# Arduino_RGB_lamp_beads.net
KiCad netlist of a schematic drawn in Altium Designer
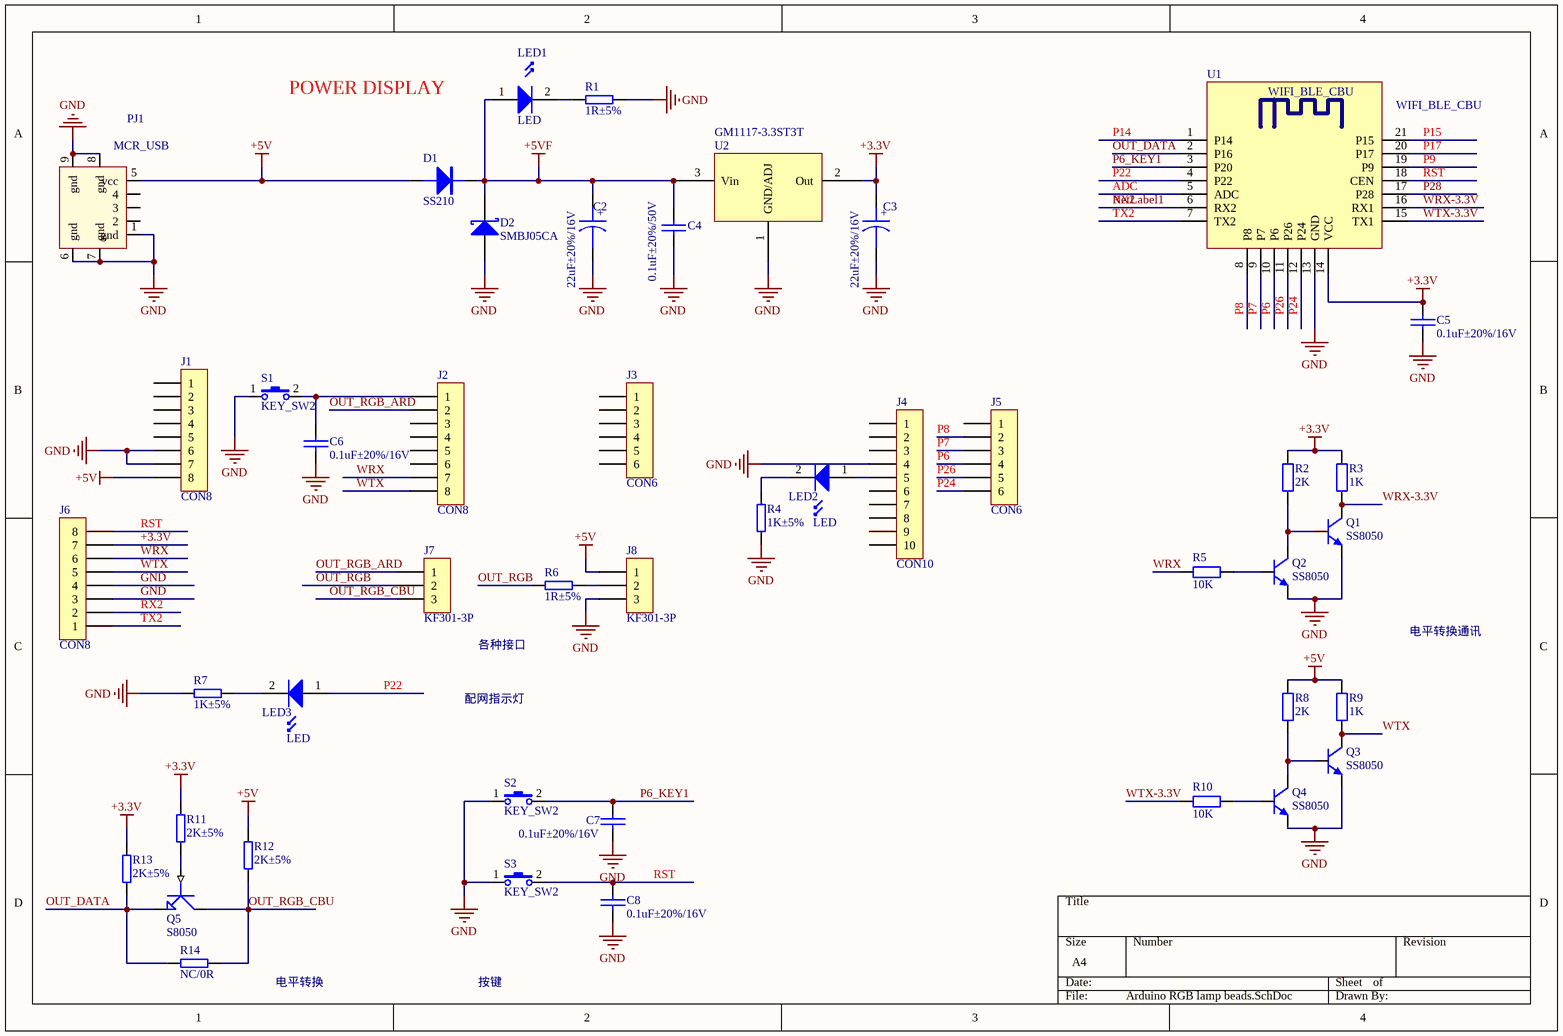
[diagram p0: Arduino RGB lamp beads.SchDoc]

(export (version "E")
  (design (tool "Eeschema 10.0.6"))
  (components
    (comp (ref "C2")
      (value "22uF±20%/16V")
      (footprint "CD B(3528)")
      (description "Capacitor")
      (libsource (lib "*") (part "CAPACITOR POL"))
    )
    (comp (ref "C3")
      (value "22uF±20%/16V")
      (footprint "CD B(3528)")
      (description "Capacitor")
      (libsource (lib "*") (part "CAPACITOR POL"))
    )
    (comp (ref "C4")
      (value "0.1uF±20%/50V")
      (footprint "C 0603_M")
      (description "Capacitor")
      (libsource (lib "昊华元件库sch") (part "CAP"))
    )
    (comp (ref "C5")
      (value "0.1uF±20%/16V")
      (footprint "C 0603_M")
      (description "Capacitor")
      (libsource (lib "昊华元件库sch") (part "CAP"))
    )
    (comp (ref "C6")
      (value "0.1uF±20%/16V")
      (footprint "C 0603_M")
      (description "Capacitor")
      (libsource (lib "昊华元件库sch") (part "CAP"))
    )
    (comp (ref "C7")
      (value "0.1uF±20%/16V")
      (footprint "C 0603_M")
      (description "Capacitor")
      (libsource (lib "昊华元件库sch") (part "CAP"))
    )
    (comp (ref "C8")
      (value "0.1uF±20%/16V")
      (footprint "C 0603_M")
      (description "Capacitor")
      (libsource (lib "昊华元件库sch") (part "CAP"))
    )
    (comp (ref "D1")
      (value "SS210")
      (footprint "SMB")
      (description "Diode")
      (libsource (lib "小马元件库sch") (part "Diode1"))
    )
    (comp (ref "D2")
      (value "SMBJ05CA")
      (footprint "SMB")
      (description "Schottky Diode")
      (fields (field (name "MFR") "Toshiba"))
      (libsource (lib "Miscellaneous Devices") (part "D Schottky"))
    )
    (comp (ref "J1")
      (value "CON8")
      (footprint "HDR2.54-LI-8P")
      (description "Connector")
      (libsource (lib "小马元件库sch") (part "CON8"))
    )
    (comp (ref "J2")
      (value "CON8")
      (footprint "HDR2.54-LI-8P")
      (description "Connector")
      (libsource (lib "小马元件库sch") (part "CON8"))
    )
    (comp (ref "J3")
      (value "CON6")
      (footprint "HDR2.54-LI-6P")
      (description "Connector")
      (libsource (lib "小马元件库sch") (part "CON6"))
    )
    (comp (ref "J4")
      (value "CON10")
      (footprint "HDR2.54-LI-10P")
      (description "Connector")
      (libsource (lib "小马元件库sch") (part "CON10"))
    )
    (comp (ref "J5")
      (value "CON6")
      (footprint "HDR2.54-LI-6P")
      (description "Connector")
      (libsource (lib "小马元件库sch") (part "CON6"))
    )
    (comp (ref "J6")
      (value "CON8")
      (footprint "HDR2.54-LI-8P")
      (description "Connector")
      (libsource (lib "") (part "CON8_1"))
    )
    (comp (ref "J7")
      (value "KF301-3P")
      (footprint "XH2.54-LI-3P")
      (description "Connector")
      (libsource (lib "小马元件库sch") (part "CON3"))
    )
    (comp (ref "J8")
      (value "KF301-3P")
      (footprint "XH2.54-LI-3P")
      (description "Connector")
      (libsource (lib "小马元件库sch") (part "CON3"))
    )
    (comp (ref "LED1")
      (value "LED")
      (footprint "LED 0603G")
      (fields (field (name "PUBLISHER") "*"))
      (libsource (lib "小马元件库sch") (part "LED"))
    )
    (comp (ref "LED2")
      (value "LED")
      (footprint "LED 0603G")
      (fields (field (name "PUBLISHER") "*"))
      (libsource (lib "小马元件库sch") (part "LED"))
    )
    (comp (ref "LED3")
      (value "LED")
      (footprint "LED 0603G")
      (fields (field (name "PUBLISHER") "*"))
      (libsource (lib "小马元件库sch") (part "LED"))
    )
    (comp (ref "PJ1")
      (value "MCR_USB")
      (footprint "USB-MICRO_E")
      (fields (field (name "PUBLISHER") "*"))
      (libsource (lib "昊华元件库sch") (part "MCR_USB"))
    )
    (comp (ref "Q1")
      (value "SS8050")
      (footprint "SOT23-3M")
      (description "高频放大-NPN型")
      (fields (field (name "版权归属") "源创客"))
      (libsource (lib "6.2   - 三极管") (part "8050-SMD"))
    )
    (comp (ref "Q2")
      (value "SS8050")
      (footprint "SOT23-3M")
      (description "高频放大-NPN型")
      (fields (field (name "版权归属") "源创客"))
      (libsource (lib "6.2   - 三极管") (part "8050-SMD"))
    )
    (comp (ref "Q3")
      (value "SS8050")
      (footprint "SOT23-3M")
      (description "高频放大-NPN型")
      (fields (field (name "版权归属") "源创客"))
      (libsource (lib "6.2   - 三极管") (part "8050-SMD"))
    )
    (comp (ref "Q4")
      (value "SS8050")
      (footprint "SOT23-3M")
      (description "高频放大-NPN型")
      (fields (field (name "版权归属") "源创客"))
      (libsource (lib "6.2   - 三极管") (part "8050-SMD"))
    )
    (comp (ref "Q5")
      (value "S8050")
      (footprint "SOT-23-NPN")
      (description "NPN Transistor")
      (libsource (lib "小马元件库sch") (part "NPN"))
    )
    (comp (ref "R1") (value "1R±5%") (footprint "R 0603_M") (libsource (lib "昊华元件库sch") (part "RES5")))
    (comp (ref "R2")
      (value "2K")
      (footprint "R 0603_M")
      (description "贴片电阻")
      (fields (field (name "版权归属") "源创客"))
      (libsource (lib "3.1   - 电阻-电容-电感") (part "R"))
    )
    (comp (ref "R3")
      (value "1K")
      (footprint "R 0603_M")
      (description "贴片电阻")
      (fields (field (name "版权归属") "源创客"))
      (libsource (lib "3.1   - 电阻-电容-电感") (part "R"))
    )
    (comp (ref "R4") (value "1K±5%") (footprint "R 0603_M") (libsource (lib "昊华元件库sch") (part "RES5")))
    (comp (ref "R5")
      (value "10K")
      (footprint "R 0603_M")
      (description "贴片电阻")
      (fields (field (name "版权归属") "源创客"))
      (libsource (lib "3.1   - 电阻-电容-电感") (part "R"))
    )
    (comp (ref "R6") (value "1R±5%") (footprint "R 0603_M") (libsource (lib "昊华元件库sch") (part "RES5")))
    (comp (ref "R7") (value "1K±5%") (footprint "R 0603_M") (libsource (lib "昊华元件库sch") (part "RES5")))
    (comp (ref "R8")
      (value "2K")
      (footprint "R 0603_M")
      (description "贴片电阻")
      (fields (field (name "版权归属") "源创客"))
      (libsource (lib "3.1   - 电阻-电容-电感") (part "R"))
    )
    (comp (ref "R9")
      (value "1K")
      (footprint "R 0603_M")
      (description "贴片电阻")
      (fields (field (name "版权归属") "源创客"))
      (libsource (lib "3.1   - 电阻-电容-电感") (part "R"))
    )
    (comp (ref "R10")
      (value "10K")
      (footprint "R 0603_M")
      (description "贴片电阻")
      (fields (field (name "版权归属") "源创客"))
      (libsource (lib "3.1   - 电阻-电容-电感") (part "R"))
    )
    (comp (ref "R11") (value "2K±5%") (footprint "R 0603_M") (libsource (lib "昊华元件库sch") (part "RES5")))
    (comp (ref "R12") (value "2K±5%") (footprint "R 0603_M") (libsource (lib "昊华元件库sch") (part "RES5")))
    (comp (ref "R13") (value "2K±5%") (footprint "R 0603_M") (libsource (lib "昊华元件库sch") (part "RES5")))
    (comp (ref "R14") (value "NC/0R") (footprint "R 0603_M") (libsource (lib "昊华元件库sch") (part "RES5")))
    (comp (ref "S1")
      (value "KEY_SW2")
      (footprint "TSW SMD-4*4*1.5")
      (libsource (lib "小马元件库sch") (part "KEY_SW2"))
    )
    (comp (ref "S2") (value "KEY_SW2") (footprint "KEY4-SMD") (libsource (lib "小马元件库sch") (part "KEY_SW2")))
    (comp (ref "S3") (value "KEY_SW2") (footprint "KEY4-SMD") (libsource (lib "小马元件库sch") (part "KEY_SW2")))
    (comp (ref "U1")
      (value "WIFI_BLE_CBU")
      (footprint "WIFI_BLE_CBU")
      (description "Module")
      (libsource (lib "TYModeSchlib V03") (part "WIFI_BLE_CBU"))
    )
    (comp (ref "U2") (value "GM1117-3.3ST3T") (footprint "SOT-223") (libsource (lib "mylib") (part "GM1117")))
  )
  (nets
    (net (code "1") (name "+3.3V") (class "Default")
      (node (ref "C3") (pin "1") (pinfunction "1_1") (pintype "passive"))
      (node (ref "C5") (pin "2") (pinfunction "2_2") (pintype "passive"))
      (node (ref "J6") (pin "7") (pinfunction "7_7") (pintype "passive"))
      (node (ref "R11") (pin "1") (pinfunction "1_1") (pintype "passive"))
      (node (ref "R13") (pin "1") (pinfunction "1_1") (pintype "passive"))
      (node (ref "R2") (pin "1") (pinfunction "1_1") (pintype "passive"))
      (node (ref "R3") (pin "1") (pinfunction "1_1") (pintype "passive"))
      (node (ref "U1") (pin "14") (pinfunction "VCC_14") (pintype "passive"))
      (node (ref "U2") (pin "2") (pinfunction "Out_2") (pintype "passive"))
    )
    (net (code "2") (name "+5V") (class "Default")
      (node (ref "D1") (pin "1") (pinfunction "1_1") (pintype "passive"))
      (node (ref "J1") (pin "8") (pinfunction "8_8") (pintype "passive"))
      (node (ref "J8") (pin "1") (pinfunction "1_1") (pintype "passive"))
      (node (ref "PJ1") (pin "5") (pinfunction "vcc_5") (pintype "passive"))
      (node (ref "R12") (pin "1") (pinfunction "1_1") (pintype "passive"))
      (node (ref "R8") (pin "1") (pinfunction "1_1") (pintype "passive"))
      (node (ref "R9") (pin "1") (pinfunction "1_1") (pintype "passive"))
    )
    (net (code "3") (name "+5VF") (class "Default")
      (node (ref "C2") (pin "1") (pinfunction "1_1") (pintype "passive"))
      (node (ref "C4") (pin "1") (pinfunction "1_1") (pintype "passive"))
      (node (ref "D1") (pin "2") (pinfunction "2_2") (pintype "passive"))
      (node (ref "D2") (pin "2") (pinfunction "K_2") (pintype "passive"))
      (node (ref "LED1") (pin "1") (pinfunction "1_1") (pintype "passive"))
      (node (ref "U2") (pin "3") (pinfunction "Vin_3") (pintype "passive"))
    )
    (net (code "4") (name "/ADC") (class "Default")
      (node (ref "U1") (pin "5") (pinfunction "ADC_5") (pintype "passive"))
    )
    (net (code "5") (name "/NetLabel1") (class "Default")
      (node (ref "J6") (pin "2") (pinfunction "2_2") (pintype "passive"))
      (node (ref "U1") (pin "6") (pinfunction "RX2_6") (pintype "passive"))
    )
    (net (code "6") (name "/OUT_DATA") (class "Default")
      (node (ref "Q5") (pin "1") (pinfunction "E_1") (pintype "passive"))
      (node (ref "R13") (pin "2") (pinfunction "2_2") (pintype "passive"))
      (node (ref "R14") (pin "1") (pinfunction "1_1") (pintype "passive"))
      (node (ref "U1") (pin "2") (pinfunction "P16_2") (pintype "passive"))
    )
    (net (code "7") (name "/OUT_RGB") (class "Default")
      (node (ref "J7") (pin "2") (pinfunction "2_2") (pintype "passive"))
      (node (ref "R6") (pin "1") (pinfunction "1_1") (pintype "passive"))
    )
    (net (code "8") (name "/OUT_RGB_ARD") (class "Default")
      (node (ref "J2") (pin "2") (pinfunction "2_2") (pintype "passive"))
      (node (ref "J7") (pin "1") (pinfunction "1_1") (pintype "passive"))
    )
    (net (code "9") (name "/OUT_RGB_CBU") (class "Default")
      (node (ref "J7") (pin "3") (pinfunction "3_3") (pintype "passive"))
      (node (ref "Q5") (pin "3") (pinfunction "C_3") (pintype "passive"))
      (node (ref "R12") (pin "2") (pinfunction "2_2") (pintype "passive"))
      (node (ref "R14") (pin "2") (pinfunction "2_2") (pintype "passive"))
    )
    (net (code "10") (name "/P6") (class "Default")
      (node (ref "J5") (pin "4") (pinfunction "4_4") (pintype "passive"))
      (node (ref "U1") (pin "10") (pinfunction "P6_10") (pintype "passive"))
    )
    (net (code "11") (name "/P6_KEY1") (class "Default")
      (node (ref "C7") (pin "2") (pinfunction "2_2") (pintype "passive"))
      (node (ref "S2") (pin "2") (pinfunction "2_2") (pintype "passive"))
      (node (ref "U1") (pin "3") (pinfunction "P20_3") (pintype "passive"))
    )
    (net (code "12") (name "/P7") (class "Default")
      (node (ref "J5") (pin "3") (pinfunction "3_3") (pintype "passive"))
      (node (ref "U1") (pin "9") (pinfunction "P7_9") (pintype "passive"))
    )
    (net (code "13") (name "/P8") (class "Default")
      (node (ref "J5") (pin "2") (pinfunction "2_2") (pintype "passive"))
      (node (ref "U1") (pin "8") (pinfunction "P8_8") (pintype "passive"))
    )
    (net (code "14") (name "/P9") (class "Default")
      (node (ref "U1") (pin "19") (pinfunction "P9_19") (pintype "passive"))
    )
    (net (code "15") (name "/P14") (class "Default")
      (node (ref "U1") (pin "1") (pinfunction "P14_1") (pintype "passive"))
    )
    (net (code "16") (name "/P15") (class "Default")
      (node (ref "U1") (pin "21") (pinfunction "P15_21") (pintype "passive"))
    )
    (net (code "17") (name "/P17") (class "Default")
      (node (ref "U1") (pin "20") (pinfunction "P17_20") (pintype "passive"))
    )
    (net (code "18") (name "/P22") (class "Default")
      (node (ref "LED3") (pin "1") (pinfunction "1_1") (pintype "passive"))
      (node (ref "U1") (pin "4") (pinfunction "P22_4") (pintype "passive"))
    )
    (net (code "19") (name "/P24") (class "Default")
      (node (ref "J5") (pin "6") (pinfunction "6_6") (pintype "passive"))
      (node (ref "U1") (pin "12") (pinfunction "P24_12") (pintype "passive"))
    )
    (net (code "20") (name "/P26") (class "Default")
      (node (ref "J5") (pin "5") (pinfunction "5_5") (pintype "passive"))
      (node (ref "U1") (pin "11") (pinfunction "P26_11") (pintype "passive"))
    )
    (net (code "21") (name "/P28") (class "Default")
      (node (ref "U1") (pin "17") (pinfunction "P28_17") (pintype "passive"))
    )
    (net (code "22") (name "/RST") (class "Default")
      (node (ref "C8") (pin "1") (pinfunction "1_1") (pintype "passive"))
      (node (ref "J6") (pin "8") (pinfunction "8_8") (pintype "passive"))
      (node (ref "S3") (pin "2") (pinfunction "2_2") (pintype "passive"))
      (node (ref "U1") (pin "18") (pinfunction "CEN_18") (pintype "passive"))
    )
    (net (code "23") (name "/TX2") (class "Default")
      (node (ref "J6") (pin "1") (pinfunction "1_1") (pintype "passive"))
      (node (ref "U1") (pin "7") (pinfunction "TX2_7") (pintype "passive"))
    )
    (net (code "24") (name "/WRX") (class "Default")
      (node (ref "J2") (pin "7") (pinfunction "7_7") (pintype "passive"))
      (node (ref "J6") (pin "6") (pinfunction "6_6") (pintype "passive"))
      (node (ref "R5") (pin "1") (pinfunction "1_1") (pintype "passive"))
    )
    (net (code "25") (name "/WRX-3.3V") (class "Default")
      (node (ref "Q1") (pin "3") (pinfunction "C_3") (pintype "passive"))
      (node (ref "R3") (pin "2") (pinfunction "2_2") (pintype "passive"))
      (node (ref "U1") (pin "16") (pinfunction "RX1_16") (pintype "passive"))
    )
    (net (code "26") (name "/WTX") (class "Default")
      (node (ref "J2") (pin "8") (pinfunction "8_8") (pintype "passive"))
      (node (ref "J6") (pin "5") (pinfunction "5_5") (pintype "passive"))
      (node (ref "Q3") (pin "3") (pinfunction "C_3") (pintype "passive"))
      (node (ref "R9") (pin "2") (pinfunction "2_2") (pintype "passive"))
    )
    (net (code "27") (name "/WTX-3.3V") (class "Default")
      (node (ref "R10") (pin "1") (pinfunction "1_1") (pintype "passive"))
      (node (ref "U1") (pin "15") (pinfunction "TX1_15") (pintype "passive"))
    )
    (net (code "28") (name "GND") (class "Default")
      (node (ref "C2") (pin "2") (pinfunction "2_2") (pintype "passive"))
      (node (ref "C3") (pin "2") (pinfunction "2_2") (pintype "passive"))
      (node (ref "C4") (pin "2") (pinfunction "2_2") (pintype "passive"))
      (node (ref "C5") (pin "1") (pinfunction "1_1") (pintype "passive"))
      (node (ref "C6") (pin "1") (pinfunction "1_1") (pintype "passive"))
      (node (ref "C7") (pin "1") (pinfunction "1_1") (pintype "passive"))
      (node (ref "C8") (pin "2") (pinfunction "2_2") (pintype "passive"))
      (node (ref "D2") (pin "1") (pinfunction "A_1") (pintype "passive"))
      (node (ref "J1") (pin "6") (pinfunction "6_6") (pintype "passive"))
      (node (ref "J1") (pin "7") (pinfunction "7_7") (pintype "passive"))
      (node (ref "J4") (pin "4") (pinfunction "4_4") (pintype "passive"))
      (node (ref "J6") (pin "3") (pinfunction "3_3") (pintype "passive"))
      (node (ref "J6") (pin "4") (pinfunction "4_4") (pintype "passive"))
      (node (ref "J8") (pin "3") (pinfunction "3_3") (pintype "passive"))
      (node (ref "PJ1") (pin "1") (pinfunction "gnd_1") (pintype "passive"))
      (node (ref "PJ1") (pin "6") (pinfunction "gnd_6") (pintype "passive"))
      (node (ref "PJ1") (pin "7") (pinfunction "gnd_7") (pintype "passive"))
      (node (ref "PJ1") (pin "8") (pinfunction "gnd_8") (pintype "passive"))
      (node (ref "PJ1") (pin "9") (pinfunction "gnd_9") (pintype "passive"))
      (node (ref "Q1") (pin "2") (pinfunction "E_2") (pintype "passive"))
      (node (ref "Q2") (pin "2") (pinfunction "E_2") (pintype "passive"))
      (node (ref "Q3") (pin "2") (pinfunction "E_2") (pintype "passive"))
      (node (ref "Q4") (pin "2") (pinfunction "E_2") (pintype "passive"))
      (node (ref "R1") (pin "2") (pinfunction "2_2") (pintype "passive"))
      (node (ref "R4") (pin "1") (pinfunction "1_1") (pintype "passive"))
      (node (ref "R7") (pin "2") (pinfunction "2_2") (pintype "passive"))
      (node (ref "S1") (pin "1") (pinfunction "1_1") (pintype "passive"))
      (node (ref "S2") (pin "1") (pinfunction "1_1") (pintype "passive"))
      (node (ref "S3") (pin "1") (pinfunction "1_1") (pintype "passive"))
      (node (ref "U1") (pin "13") (pinfunction "GND_13") (pintype "passive"))
      (node (ref "U2") (pin "1") (pinfunction "GND/ADJ_1") (pintype "passive"))
    )
    (net (code "29") (name "Net-(C6-Pad2)") (class "Default")
      (node (ref "C6") (pin "2") (pinfunction "2_2") (pintype "passive"))
      (node (ref "J2") (pin "1") (pinfunction "1_1") (pintype "passive"))
      (node (ref "S1") (pin "2") (pinfunction "2_2") (pintype "passive"))
    )
    (net (code "30") (name "Net-(J4-Pad5)") (class "Default")
      (node (ref "J4") (pin "5") (pinfunction "5_5") (pintype "passive"))
      (node (ref "LED2") (pin "1") (pinfunction "1_1") (pintype "passive"))
    )
    (net (code "31") (name "Net-(J8-Pad2)") (class "Default")
      (node (ref "J8") (pin "2") (pinfunction "2_2") (pintype "passive"))
      (node (ref "R6") (pin "2") (pinfunction "2_2") (pintype "passive"))
    )
    (net (code "32") (name "Net-(LED1-Pad2)") (class "Default")
      (node (ref "LED1") (pin "2") (pinfunction "2_2") (pintype "passive"))
      (node (ref "R1") (pin "1") (pinfunction "1_1") (pintype "passive"))
    )
    (net (code "33") (name "Net-(LED2-Pad2)") (class "Default")
      (node (ref "LED2") (pin "2") (pinfunction "2_2") (pintype "passive"))
      (node (ref "R4") (pin "2") (pinfunction "2_2") (pintype "passive"))
    )
    (net (code "34") (name "Net-(LED3-Pad2)") (class "Default")
      (node (ref "LED3") (pin "2") (pinfunction "2_2") (pintype "passive"))
      (node (ref "R7") (pin "1") (pinfunction "1_1") (pintype "passive"))
    )
    (net (code "35") (name "Net-(Q1-B)") (class "Default")
      (node (ref "Q1") (pin "1") (pinfunction "B_1") (pintype "passive"))
      (node (ref "Q2") (pin "3") (pinfunction "C_3") (pintype "passive"))
      (node (ref "R2") (pin "2") (pinfunction "2_2") (pintype "passive"))
    )
    (net (code "36") (name "Net-(Q2-B)") (class "Default")
      (node (ref "Q2") (pin "1") (pinfunction "B_1") (pintype "passive"))
      (node (ref "R5") (pin "2") (pinfunction "2_2") (pintype "passive"))
    )
    (net (code "37") (name "Net-(Q3-B)") (class "Default")
      (node (ref "Q3") (pin "1") (pinfunction "B_1") (pintype "passive"))
      (node (ref "Q4") (pin "3") (pinfunction "C_3") (pintype "passive"))
      (node (ref "R8") (pin "2") (pinfunction "2_2") (pintype "passive"))
    )
    (net (code "38") (name "Net-(Q4-B)") (class "Default")
      (node (ref "Q4") (pin "1") (pinfunction "B_1") (pintype "passive"))
      (node (ref "R10") (pin "2") (pinfunction "2_2") (pintype "passive"))
    )
    (net (code "39") (name "Net-(Q5-B)") (class "Default")
      (node (ref "Q5") (pin "2") (pinfunction "B_2") (pintype "input"))
      (node (ref "R11") (pin "2") (pinfunction "2_2") (pintype "passive"))
    )
    (net (code "40") (name "unconnected-(J1-Pad1)") (class "Default")
      (node (ref "J1") (pin "1") (pinfunction "1_1") (pintype "passive"))
    )
    (net (code "41") (name "unconnected-(J1-Pad2)") (class "Default")
      (node (ref "J1") (pin "2") (pinfunction "2_2") (pintype "passive"))
    )
    (net (code "42") (name "unconnected-(J1-Pad3)") (class "Default")
      (node (ref "J1") (pin "3") (pinfunction "3_3") (pintype "passive"))
    )
    (net (code "43") (name "unconnected-(J1-Pad4)") (class "Default")
      (node (ref "J1") (pin "4") (pinfunction "4_4") (pintype "passive"))
    )
    (net (code "44") (name "unconnected-(J1-Pad5)") (class "Default")
      (node (ref "J1") (pin "5") (pinfunction "5_5") (pintype "passive"))
    )
    (net (code "45") (name "unconnected-(J2-Pad3)") (class "Default")
      (node (ref "J2") (pin "3") (pinfunction "3_3") (pintype "passive"))
    )
    (net (code "46") (name "unconnected-(J2-Pad4)") (class "Default")
      (node (ref "J2") (pin "4") (pinfunction "4_4") (pintype "passive"))
    )
    (net (code "47") (name "unconnected-(J2-Pad5)") (class "Default")
      (node (ref "J2") (pin "5") (pinfunction "5_5") (pintype "passive"))
    )
    (net (code "48") (name "unconnected-(J2-Pad6)") (class "Default")
      (node (ref "J2") (pin "6") (pinfunction "6_6") (pintype "passive"))
    )
    (net (code "49") (name "unconnected-(J3-Pad1)") (class "Default")
      (node (ref "J3") (pin "1") (pinfunction "1_1") (pintype "passive"))
    )
    (net (code "50") (name "unconnected-(J3-Pad2)") (class "Default")
      (node (ref "J3") (pin "2") (pinfunction "2_2") (pintype "passive"))
    )
    (net (code "51") (name "unconnected-(J3-Pad3)") (class "Default")
      (node (ref "J3") (pin "3") (pinfunction "3_3") (pintype "passive"))
    )
    (net (code "52") (name "unconnected-(J3-Pad4)") (class "Default")
      (node (ref "J3") (pin "4") (pinfunction "4_4") (pintype "passive"))
    )
    (net (code "53") (name "unconnected-(J3-Pad5)") (class "Default")
      (node (ref "J3") (pin "5") (pinfunction "5_5") (pintype "passive"))
    )
    (net (code "54") (name "unconnected-(J3-Pad6)") (class "Default")
      (node (ref "J3") (pin "6") (pinfunction "6_6") (pintype "passive"))
    )
    (net (code "55") (name "unconnected-(J4-Pad1)") (class "Default")
      (node (ref "J4") (pin "1") (pinfunction "1_1") (pintype "passive"))
    )
    (net (code "56") (name "unconnected-(J4-Pad2)") (class "Default")
      (node (ref "J4") (pin "2") (pinfunction "2_2") (pintype "passive"))
    )
    (net (code "57") (name "unconnected-(J4-Pad3)") (class "Default")
      (node (ref "J4") (pin "3") (pinfunction "3_3") (pintype "passive"))
    )
    (net (code "58") (name "unconnected-(J4-Pad6)") (class "Default")
      (node (ref "J4") (pin "6") (pinfunction "6_6") (pintype "passive"))
    )
    (net (code "59") (name "unconnected-(J4-Pad7)") (class "Default")
      (node (ref "J4") (pin "7") (pinfunction "7_7") (pintype "passive"))
    )
    (net (code "60") (name "unconnected-(J4-Pad8)") (class "Default")
      (node (ref "J4") (pin "8") (pinfunction "8_8") (pintype "passive"))
    )
    (net (code "61") (name "unconnected-(J4-Pad9)") (class "Default")
      (node (ref "J4") (pin "9") (pinfunction "9_9") (pintype "passive"))
    )
    (net (code "62") (name "unconnected-(J4-Pad10)") (class "Default")
      (node (ref "J4") (pin "10") (pinfunction "10_10") (pintype "passive"))
    )
    (net (code "63") (name "unconnected-(J5-Pad1)") (class "Default")
      (node (ref "J5") (pin "1") (pinfunction "1_1") (pintype "passive"))
    )
    (net (code "64") (name "unconnected-(PJ1-Pad2)") (class "Default")
      (node (ref "PJ1") (pin "2") (pinfunction "2_2") (pintype "passive"))
    )
    (net (code "65") (name "unconnected-(PJ1-Pad3)") (class "Default")
      (node (ref "PJ1") (pin "3") (pinfunction "3_3") (pintype "passive"))
    )
    (net (code "66") (name "unconnected-(PJ1-Pad4)") (class "Default")
      (node (ref "PJ1") (pin "4") (pinfunction "4_4") (pintype "passive"))
    )
  )
)
